# Power.net
KiCad netlist of a schematic drawn in Altium Designer
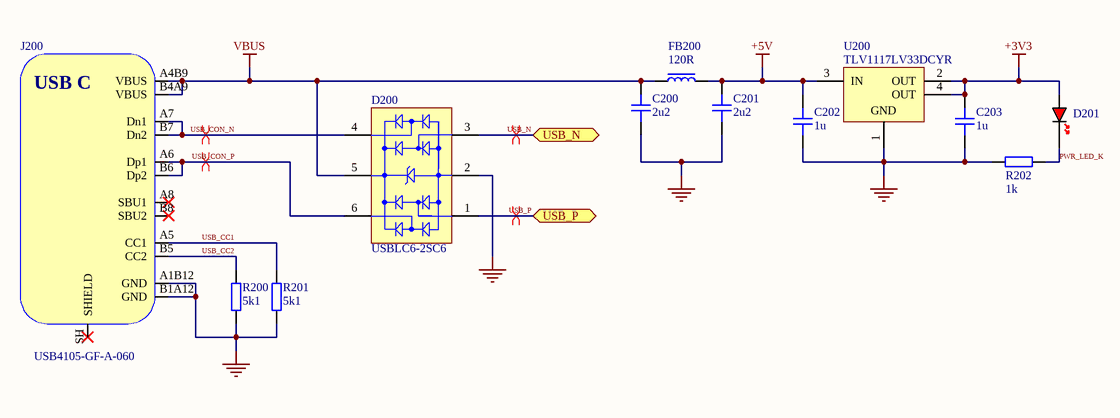
[diagram p0: Power.SchDoc]

(export (version "E")
  (design (tool "Eeschema 10.0.6"))
  (components
    (comp (ref "C200")
      (value "2u2")
      (footprint "CAP_0805")
      (description "Capacitor SMD 0805 16V")
      (libsource (lib "Schematic-Lib-PhilsLab") (part "CAP_0805_16V"))
    )
    (comp (ref "C201")
      (value "2u2")
      (footprint "CAP_0805")
      (description "Capacitor SMD 0805 16V")
      (libsource (lib "Schematic-Lib-PhilsLab") (part "CAP_0805_16V"))
    )
    (comp (ref "C202")
      (value "1u")
      (footprint "CAP_0805")
      (description "Capacitor SMD 0805 16V")
      (libsource (lib "Schematic-Lib-PhilsLab") (part "CAP_0805_16V"))
    )
    (comp (ref "C203")
      (value "1u")
      (footprint "CAP_0805")
      (description "Capacitor SMD 0805 16V")
      (libsource (lib "Schematic-Lib-PhilsLab") (part "CAP_0805_16V"))
    )
    (comp (ref "D200")
      (value "USBLC6-2SC6")
      (footprint "STM-SOT23-6L_V")
      (description "Very low capacitance ESD protection, 3.5 pF, -40 to 125 degC, 6-Pin SOT23, RoHS, Tape and Reel")
      (fields (field (name "MANUFACTURER") "STMicroelectronics"))
      (libsource (lib "Altium Content Vault") (part "STM-USB_DVI_HDMIULC6-4SC6X-SOT23-6L"))
    )
    (comp (ref "D201")
      (value "RED")
      (footprint "LED_0603_RED")
      (description "LED 0603 RED SMD")
      (libsource (lib "Schematic-Lib-PhilsLab") (part "LED_0603_RED"))
    )
    (comp (ref "FB200")
      (value "120R")
      (footprint "FB_0603")
      (description "Ferrite Bead SMD 0603")
      (libsource (lib "Schematic-Lib-PhilsLab") (part "FB_0603"))
    )
    (comp (ref "J200")
      (value "USB4105-GF-A-060")
      (footprint "USB4105-GF-A-060")
      (description "USB Connector Type C SMT 12 Pin")
      (fields (field (name "MANUFACTURER") "GCT"))
      (libsource (lib "Schematic-Lib-PhilsLab") (part "USB4105-GF-A-060"))
    )
    (comp (ref "R200")
      (value "5k1")
      (footprint "RES_0603")
      (description "Resistor SMD 0603")
      (libsource (lib "Schematic-Lib-PhilsLab") (part "RES_0603"))
    )
    (comp (ref "R201")
      (value "5k1")
      (footprint "RES_0603")
      (description "Resistor SMD 0603")
      (libsource (lib "Schematic-Lib-PhilsLab") (part "RES_0603"))
    )
    (comp (ref "R202")
      (value "1k")
      (footprint "RES_0603")
      (description "Resistor SMD 0603")
      (libsource (lib "Schematic-Lib-PhilsLab") (part "RES_0603"))
    )
    (comp (ref "U200")
      (value "TLV1117LV33DCYR")
      (footprint "DCY0004A_N")
      (fields (field (name "MANUFACTURER") "Texas Instruments"))
      (libsource (lib "Altium Content Vault") (part "TI-TLV1117LV33DCY4"))
    )
  )
  (nets
    (net (code "1") (name "+3V3") (class "Default")
      (node (ref "C203") (pin "1") (pinfunction "1_1") (pintype "passive"))
      (node (ref "D201") (pin "A") (pinfunction "A_A") (pintype "passive"))
      (node (ref "U200") (pin "2") (pinfunction "OUT_2") (pintype "power_in"))
      (node (ref "U200") (pin "4") (pinfunction "OUT_4") (pintype "power_in"))
    )
    (net (code "2") (name "+5V") (class "Default")
      (node (ref "C201") (pin "1") (pinfunction "1_1") (pintype "passive"))
      (node (ref "C202") (pin "1") (pinfunction "1_1") (pintype "passive"))
      (node (ref "FB200") (pin "2") (pinfunction "2_2") (pintype "passive"))
      (node (ref "U200") (pin "3") (pinfunction "IN_3") (pintype "power_in"))
    )
    (net (code "3") (name "/PWR_LED_K") (class "Default")
      (node (ref "D201") (pin "K") (pinfunction "K_K") (pintype "passive"))
      (node (ref "R202") (pin "1") (pinfunction "1_1") (pintype "passive"))
    )
    (net (code "4") (name "/USB_CC1") (class "Default")
      (node (ref "J200") (pin "A5") (pinfunction "CC1_A5") (pintype "passive"))
      (node (ref "R201") (pin "2") (pinfunction "2_2") (pintype "passive"))
    )
    (net (code "5") (name "/USB_CC2") (class "Default")
      (node (ref "J200") (pin "B5") (pinfunction "CC2_B5") (pintype "passive"))
      (node (ref "R200") (pin "2") (pinfunction "2_2") (pintype "passive"))
    )
    (net (code "6") (name "/USB_CON_N") (class "Default")
      (node (ref "D200") (pin "4") (pinfunction "I/O_3_4") (pintype "passive"))
      (node (ref "J200") (pin "A7") (pinfunction "Dn1_A7") (pintype "passive"))
      (node (ref "J200") (pin "B7") (pinfunction "Dn2_B7") (pintype "passive"))
    )
    (net (code "7") (name "/USB_CON_P") (class "Default")
      (node (ref "D200") (pin "6") (pinfunction "I/O_4_6") (pintype "passive"))
      (node (ref "J200") (pin "A6") (pinfunction "Dp1_A6") (pintype "passive"))
      (node (ref "J200") (pin "B6") (pinfunction "Dp2_B6") (pintype "passive"))
    )
    (net (code "8") (name "/USB_N") (class "Default")
      (node (ref "D200") (pin "3") (pinfunction "I/O_2_3") (pintype "passive"))
    )
    (net (code "9") (name "/USB_P") (class "Default")
      (node (ref "D200") (pin "1") (pinfunction "I/O_1_1") (pintype "passive"))
    )
    (net (code "10") (name "GND") (class "Default")
      (node (ref "C200") (pin "1") (pinfunction "1_1") (pintype "passive"))
      (node (ref "C201") (pin "2") (pinfunction "2_2") (pintype "passive"))
      (node (ref "C202") (pin "2") (pinfunction "2_2") (pintype "passive"))
      (node (ref "C203") (pin "2") (pinfunction "2_2") (pintype "passive"))
      (node (ref "D200") (pin "2") (pinfunction "GND_2") (pintype "passive"))
      (node (ref "J200") (pin "A1B12") (pinfunction "GND_A1B12") (pintype "passive"))
      (node (ref "J200") (pin "B1A12") (pinfunction "GND_B1A12") (pintype "passive"))
      (node (ref "R200") (pin "1") (pinfunction "1_1") (pintype "passive"))
      (node (ref "R201") (pin "1") (pinfunction "1_1") (pintype "passive"))
      (node (ref "R202") (pin "2") (pinfunction "2_2") (pintype "passive"))
      (node (ref "U200") (pin "1") (pinfunction "GND_1") (pintype "power_in"))
    )
    (net (code "11") (name "VBUS") (class "Default")
      (node (ref "C200") (pin "2") (pinfunction "2_2") (pintype "passive"))
      (node (ref "D200") (pin "5") (pinfunction "VBUS_5") (pintype "passive"))
      (node (ref "FB200") (pin "1") (pinfunction "1_1") (pintype "passive"))
      (node (ref "J200") (pin "A4B9") (pinfunction "VBUS_A4B9") (pintype "passive"))
      (node (ref "J200") (pin "B4A9") (pinfunction "VBUS_B4A9") (pintype "passive"))
    )
    (net (code "12") (name "unconnected-(J200-SBU1-PadA8)") (class "Default")
      (node (ref "J200") (pin "A8") (pinfunction "SBU1_A8") (pintype "passive+no_connect"))
    )
    (net (code "13") (name "unconnected-(J200-SBU2-PadB8)") (class "Default")
      (node (ref "J200") (pin "B8") (pinfunction "SBU2_B8") (pintype "passive+no_connect"))
    )
    (net (code "14") (name "unconnected-(J200-SHIELD-PadSH)") (class "Default")
      (node (ref "J200") (pin "SH") (pinfunction "SHIELD_SH") (pintype "passive+no_connect"))
    )
  )
)
